# Sheet1.net
KiCad netlist of a schematic drawn in Altium Designer
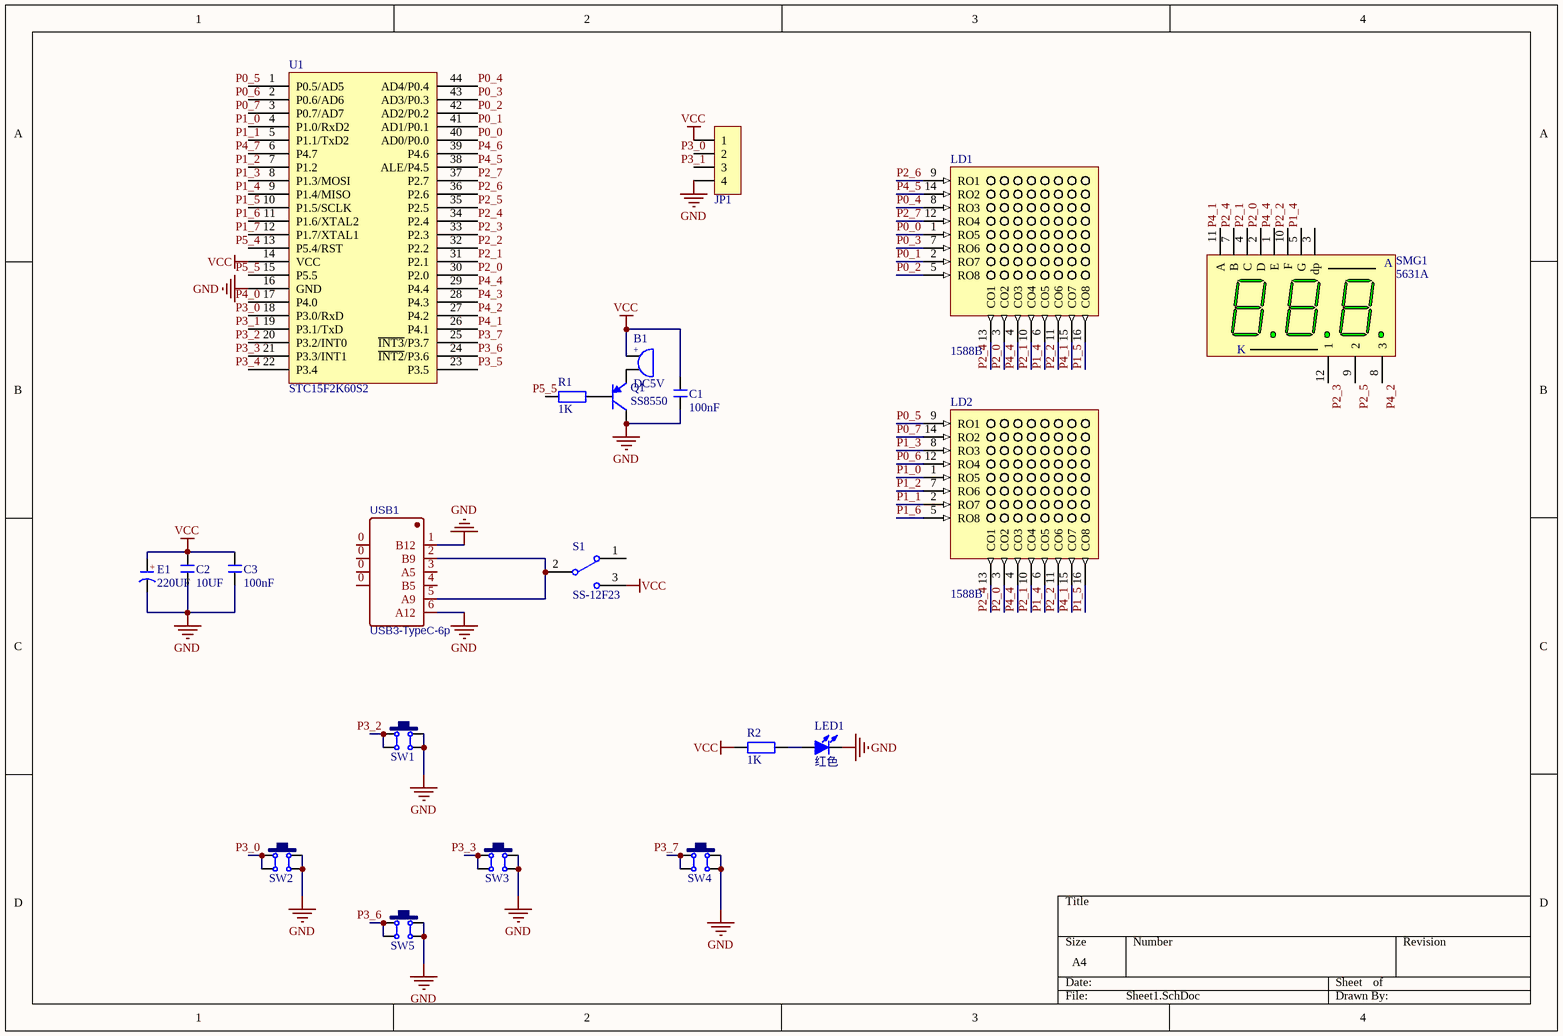
[diagram p0: Sheet1.SchDoc]

(export (version "E")
  (design (tool "Eeschema 10.0.6"))
  (components
    (comp (ref "B1")
      (value "DC5V")
      (footprint "BEEP 5x9x5.5")
      (description "蜂鸣器")
      (fields (field (name "版权归属") "黎明电子style"))
      (libsource (lib "1.7.1-未分类器件") (part "BEEP"))
    )
    (comp (ref "C1")
      (value "100nF")
      (footprint "C 0805")
      (description "无极性贴片电容")
      (fields (field (name "版权归属") "黎明电子style"))
      (libsource (lib "1.3.2-电阻_电容_电感") (part "C"))
    )
    (comp (ref "C2")
      (value "10UF")
      (footprint "C 0805")
      (description "无极性贴片电容")
      (fields (field (name "版权归属") "黎明电子style"))
      (libsource (lib "1.3.2-电阻_电容_电感") (part "C"))
    )
    (comp (ref "C3")
      (value "100nF")
      (footprint "C 0805")
      (description "无极性贴片电容")
      (fields (field (name "版权归属") "黎明电子style"))
      (libsource (lib "1.3.2-电阻_电容_电感") (part "C"))
    )
    (comp (ref "E1")
      (value "220UF")
      (footprint "CAP 2.5*5*11 - BK")
      (description "直插电解电容")
      (fields (field (name "版权归属") "黎明电子style"))
      (libsource (lib "1.3.2-电阻_电容_电感") (part "C-CAP"))
    )
    (comp (ref "JP1")
      (value "HDR-1X4")
      (footprint "HDR2.54-WS-4P")
      (description "4P接插件")
      (fields (field (name "版权归属") "黎明电子style"))
      (libsource (lib "1.5.1-接插件") (part "Header 4"))
    )
    (comp (ref "LD1")
      (value "1588B")
      (footprint "LED 8*8-38")
      (description "共阳单色LED8*8点阵屏")
      (fields (field (name "版权归属") "黎明电子style"))
      (libsource (lib "1.6.6-点阵屏_屏幕") (part "1588B"))
    )
    (comp (ref "LD2")
      (value "1588B")
      (footprint "LED 8*8-38")
      (description "共阳单色LED8*8点阵屏")
      (fields (field (name "版权归属") "黎明电子style"))
      (libsource (lib "1.6.6-点阵屏_屏幕") (part "1588B"))
    )
    (comp (ref "LED1")
      (value "红色")
      (footprint "LED 0805G")
      (description "贴片LED")
      (fields (field (name "版权归属") "黎明电子style"))
      (libsource (lib "1.3.1-LED") (part "LED-SMD"))
    )
    (comp (ref "Q1")
      (value "SS8550")
      (footprint "SOT23-3M")
      (description "高频放大-PNP型")
      (fields (field (name "版权归属") "源创客"))
      (libsource (lib "1.3.4-三极管") (part "8550-SMD"))
    )
    (comp (ref "R1")
      (value "1K")
      (footprint "R 0805")
      (description "贴片电阻")
      (fields (field (name "版权归属") "黎明电子style"))
      (libsource (lib "1.3.2-电阻_电容_电感") (part "R"))
    )
    (comp (ref "R2")
      (value "1K")
      (footprint "R 0805")
      (description "贴片电阻")
      (fields (field (name "版权归属") "黎明电子style"))
      (libsource (lib "1.3.2-电阻_电容_电感") (part "R"))
    )
    (comp (ref "S1")
      (value "SS-12F23")
      (footprint "SS-12D10")
      (description "1路波动开关")
      (fields (field (name "版权归属") "黎明电子style"))
      (libsource (lib "1.4.1-按键-开关") (part "SSW-1P"))
    )
    (comp (ref "SMG1")
      (value "5631A")
      (footprint "SMG 0.56-3P")
      (description "0.56寸3位共阴数码管")
      (fields (field (name "版权归属") "黎明电子style"))
      (libsource (lib "1.6.5-数码管") (part "5631A"))
    )
    (comp (ref "SW1")
      (value "6x6x5")
      (footprint "TSW DIP-6*6*6")
      (description "直插6x6轻触开关")
      (fields (field (name "版权归属") "黎明电子style"))
      (libsource (lib "1.4.1-按键-开关") (part "TSW DIP-6x6"))
    )
    (comp (ref "SW2")
      (value "6x6x5")
      (footprint "TSW DIP-6*6*6")
      (description "直插6x6轻触开关")
      (fields (field (name "版权归属") "黎明电子style"))
      (libsource (lib "1.4.1-按键-开关") (part "TSW DIP-6x6"))
    )
    (comp (ref "SW3")
      (value "6x6x5")
      (footprint "TSW DIP-6*6*6")
      (description "直插6x6轻触开关")
      (fields (field (name "版权归属") "黎明电子style"))
      (libsource (lib "1.4.1-按键-开关") (part "TSW DIP-6x6"))
    )
    (comp (ref "SW4")
      (value "6x6x5")
      (footprint "TSW DIP-6*6*6")
      (description "直插6x6轻触开关")
      (fields (field (name "版权归属") "黎明电子style"))
      (libsource (lib "1.4.1-按键-开关") (part "TSW DIP-6x6"))
    )
    (comp (ref "SW5")
      (value "6x6x5")
      (footprint "TSW DIP-6*6*6")
      (description "直插6x6轻触开关")
      (fields (field (name "版权归属") "黎明电子style"))
      (libsource (lib "1.4.1-按键-开关") (part "TSW DIP-6x6"))
    )
    (comp (ref "U1")
      (value "STC15F2K60S2")
      (footprint "LQFP44 10X10_M")
      (description "STC单片机")
      (fields (field (name "版权归属") "校基地硬件部"))
      (libsource (lib "1.2.1-STC系列单片机") (part "STC15F2K60S2-44pin"))
    )
    (comp (ref "USB1")
      (value "USB3-TypeC-6p")
      (footprint "USB-TYPE-C-SMD6")
      (libsource (lib "type-c-sch") (part "USB3-TypeC-6p"))
    )
  )
  (nets
    (net (code "1") (name "/P0_0") (class "Default")
      (node (ref "LD1") (pin "1") (pinfunction "RO5_1") (pintype "input"))
      (node (ref "U1") (pin "40") (pinfunction "AD0/P0.0_40") (pintype "passive"))
    )
    (net (code "2") (name "/P0_1") (class "Default")
      (node (ref "LD1") (pin "2") (pinfunction "RO7_2") (pintype "input"))
      (node (ref "U1") (pin "41") (pinfunction "AD1/P0.1_41") (pintype "passive"))
    )
    (net (code "3") (name "/P0_2") (class "Default")
      (node (ref "LD1") (pin "5") (pinfunction "RO8_5") (pintype "input"))
      (node (ref "U1") (pin "42") (pinfunction "AD2/P0.2_42") (pintype "passive"))
    )
    (net (code "4") (name "/P0_3") (class "Default")
      (node (ref "LD1") (pin "7") (pinfunction "RO6_7") (pintype "input"))
      (node (ref "U1") (pin "43") (pinfunction "AD3/P0.3_43") (pintype "passive"))
    )
    (net (code "5") (name "/P0_4") (class "Default")
      (node (ref "LD1") (pin "8") (pinfunction "RO3_8") (pintype "input"))
      (node (ref "U1") (pin "44") (pinfunction "AD4/P0.4_44") (pintype "passive"))
    )
    (net (code "6") (name "/P0_5") (class "Default")
      (node (ref "LD2") (pin "9") (pinfunction "RO1_9") (pintype "input"))
      (node (ref "U1") (pin "1") (pinfunction "P0.5/AD5_1") (pintype "passive"))
    )
    (net (code "7") (name "/P0_6") (class "Default")
      (node (ref "LD2") (pin "12") (pinfunction "RO4_12") (pintype "input"))
      (node (ref "U1") (pin "2") (pinfunction "P0.6/AD6_2") (pintype "passive"))
    )
    (net (code "8") (name "/P0_7") (class "Default")
      (node (ref "LD2") (pin "14") (pinfunction "RO2_14") (pintype "input"))
      (node (ref "U1") (pin "3") (pinfunction "P0.7/AD7_3") (pintype "passive"))
    )
    (net (code "9") (name "/P1_0") (class "Default")
      (node (ref "LD2") (pin "1") (pinfunction "RO5_1") (pintype "input"))
      (node (ref "U1") (pin "4") (pinfunction "P1.0/RxD2_4") (pintype "passive"))
    )
    (net (code "10") (name "/P1_1") (class "Default")
      (node (ref "LD2") (pin "2") (pinfunction "RO7_2") (pintype "input"))
      (node (ref "U1") (pin "5") (pinfunction "P1.1/TxD2_5") (pintype "passive"))
    )
    (net (code "11") (name "/P1_2") (class "Default")
      (node (ref "LD2") (pin "7") (pinfunction "RO6_7") (pintype "input"))
      (node (ref "U1") (pin "7") (pinfunction "P1.2_7") (pintype "passive"))
    )
    (net (code "12") (name "/P1_3") (class "Default")
      (node (ref "LD2") (pin "8") (pinfunction "RO3_8") (pintype "input"))
      (node (ref "U1") (pin "8") (pinfunction "P1.3/MOSI_8") (pintype "passive"))
    )
    (net (code "13") (name "/P1_4") (class "Default")
      (node (ref "LD1") (pin "6") (pinfunction "CO5_6") (pintype "output"))
      (node (ref "LD2") (pin "6") (pinfunction "CO5_6") (pintype "output"))
      (node (ref "SMG1") (pin "5") (pinfunction "G_5") (pintype "passive"))
      (node (ref "U1") (pin "9") (pinfunction "P1.4/MISO_9") (pintype "passive"))
    )
    (net (code "14") (name "/P1_5") (class "Default")
      (node (ref "LD1") (pin "16") (pinfunction "CO8_16") (pintype "output"))
      (node (ref "LD2") (pin "16") (pinfunction "CO8_16") (pintype "output"))
      (node (ref "U1") (pin "10") (pinfunction "P1.5/SCLK_10") (pintype "passive"))
    )
    (net (code "15") (name "/P1_6") (class "Default")
      (node (ref "LD2") (pin "5") (pinfunction "RO8_5") (pintype "input"))
      (node (ref "U1") (pin "11") (pinfunction "P1.6/XTAL2_11") (pintype "passive"))
    )
    (net (code "16") (name "/P1_7") (class "Default")
      (node (ref "U1") (pin "12") (pinfunction "P1.7/XTAL1_12") (pintype "passive"))
    )
    (net (code "17") (name "/P2_0") (class "Default")
      (node (ref "LD1") (pin "3") (pinfunction "CO2_3") (pintype "output"))
      (node (ref "LD2") (pin "3") (pinfunction "CO2_3") (pintype "output"))
      (node (ref "SMG1") (pin "2") (pinfunction "D_2") (pintype "passive"))
      (node (ref "U1") (pin "30") (pinfunction "P2.0_30") (pintype "passive"))
    )
    (net (code "18") (name "/P2_1") (class "Default")
      (node (ref "LD1") (pin "10") (pinfunction "CO4_10") (pintype "output"))
      (node (ref "LD2") (pin "10") (pinfunction "CO4_10") (pintype "output"))
      (node (ref "SMG1") (pin "4") (pinfunction "C_4") (pintype "passive"))
      (node (ref "U1") (pin "31") (pinfunction "P2.1_31") (pintype "passive"))
    )
    (net (code "19") (name "/P2_2") (class "Default")
      (node (ref "LD1") (pin "11") (pinfunction "CO6_11") (pintype "output"))
      (node (ref "LD2") (pin "11") (pinfunction "CO6_11") (pintype "output"))
      (node (ref "SMG1") (pin "10") (pinfunction "F_10") (pintype "passive"))
      (node (ref "U1") (pin "32") (pinfunction "P2.2_32") (pintype "passive"))
    )
    (net (code "20") (name "/P2_3") (class "Default")
      (node (ref "SMG1") (pin "12") (pinfunction "1_12") (pintype "passive"))
      (node (ref "U1") (pin "33") (pinfunction "P2.3_33") (pintype "passive"))
    )
    (net (code "21") (name "/P2_4") (class "Default")
      (node (ref "LD1") (pin "13") (pinfunction "CO1_13") (pintype "output"))
      (node (ref "LD2") (pin "13") (pinfunction "CO1_13") (pintype "output"))
      (node (ref "SMG1") (pin "7") (pinfunction "B_7") (pintype "passive"))
      (node (ref "U1") (pin "34") (pinfunction "P2.4_34") (pintype "passive"))
    )
    (net (code "22") (name "/P2_5") (class "Default")
      (node (ref "SMG1") (pin "9") (pinfunction "2_9") (pintype "passive"))
      (node (ref "U1") (pin "35") (pinfunction "P2.5_35") (pintype "passive"))
    )
    (net (code "23") (name "/P2_6") (class "Default")
      (node (ref "LD1") (pin "9") (pinfunction "RO1_9") (pintype "input"))
      (node (ref "U1") (pin "36") (pinfunction "P2.6_36") (pintype "passive"))
    )
    (net (code "24") (name "/P2_7") (class "Default")
      (node (ref "LD1") (pin "12") (pinfunction "RO4_12") (pintype "input"))
      (node (ref "U1") (pin "37") (pinfunction "P2.7_37") (pintype "passive"))
    )
    (net (code "25") (name "/P3_0") (class "Default")
      (node (ref "JP1") (pin "2") (pinfunction "2_2") (pintype "passive"))
      (node (ref "SW2") (pin "1") (pinfunction "1_1") (pintype "passive"))
      (node (ref "SW2") (pin "4") (pinfunction "4_4") (pintype "passive"))
      (node (ref "U1") (pin "18") (pinfunction "P3.0/RxD_18") (pintype "passive"))
    )
    (net (code "26") (name "/P3_1") (class "Default")
      (node (ref "JP1") (pin "3") (pinfunction "3_3") (pintype "passive"))
      (node (ref "U1") (pin "19") (pinfunction "P3.1/TxD_19") (pintype "passive"))
    )
    (net (code "27") (name "/P3_2") (class "Default")
      (node (ref "SW1") (pin "1") (pinfunction "1_1") (pintype "passive"))
      (node (ref "SW1") (pin "4") (pinfunction "4_4") (pintype "passive"))
      (node (ref "U1") (pin "20") (pinfunction "P3.2/INT0_20") (pintype "passive"))
    )
    (net (code "28") (name "/P3_3") (class "Default")
      (node (ref "SW3") (pin "1") (pinfunction "1_1") (pintype "passive"))
      (node (ref "SW3") (pin "4") (pinfunction "4_4") (pintype "passive"))
      (node (ref "U1") (pin "21") (pinfunction "P3.3/INT1_21") (pintype "passive"))
    )
    (net (code "29") (name "/P3_4") (class "Default")
      (node (ref "U1") (pin "22") (pinfunction "P3.4_22") (pintype "passive"))
    )
    (net (code "30") (name "/P3_5") (class "Default")
      (node (ref "U1") (pin "23") (pinfunction "P3.5_23") (pintype "passive"))
    )
    (net (code "31") (name "/P3_6") (class "Default")
      (node (ref "SW5") (pin "1") (pinfunction "1_1") (pintype "passive"))
      (node (ref "SW5") (pin "4") (pinfunction "4_4") (pintype "passive"))
      (node (ref "U1") (pin "24") (pinfunction "~{INT2}/P3.6_24") (pintype "passive"))
    )
    (net (code "32") (name "/P3_7") (class "Default")
      (node (ref "SW4") (pin "1") (pinfunction "1_1") (pintype "passive"))
      (node (ref "SW4") (pin "4") (pinfunction "4_4") (pintype "passive"))
      (node (ref "U1") (pin "25") (pinfunction "~{INT3}/P3.7_25") (pintype "passive"))
    )
    (net (code "33") (name "/P4_0") (class "Default")
      (node (ref "U1") (pin "17") (pinfunction "P4.0_17") (pintype "passive"))
    )
    (net (code "34") (name "/P4_1") (class "Default")
      (node (ref "LD1") (pin "15") (pinfunction "CO7_15") (pintype "output"))
      (node (ref "LD2") (pin "15") (pinfunction "CO7_15") (pintype "output"))
      (node (ref "SMG1") (pin "11") (pinfunction "A_11") (pintype "passive"))
      (node (ref "U1") (pin "26") (pinfunction "P4.1_26") (pintype "passive"))
    )
    (net (code "35") (name "/P4_2") (class "Default")
      (node (ref "SMG1") (pin "8") (pinfunction "3_8") (pintype "passive"))
      (node (ref "U1") (pin "27") (pinfunction "P4.2_27") (pintype "passive"))
    )
    (net (code "36") (name "/P4_3") (class "Default")
      (node (ref "U1") (pin "28") (pinfunction "P4.3_28") (pintype "passive"))
    )
    (net (code "37") (name "/P4_4") (class "Default")
      (node (ref "LD1") (pin "4") (pinfunction "CO3_4") (pintype "output"))
      (node (ref "LD2") (pin "4") (pinfunction "CO3_4") (pintype "output"))
      (node (ref "SMG1") (pin "1") (pinfunction "E_1") (pintype "passive"))
      (node (ref "U1") (pin "29") (pinfunction "P4.4_29") (pintype "passive"))
    )
    (net (code "38") (name "/P4_5") (class "Default")
      (node (ref "LD1") (pin "14") (pinfunction "RO2_14") (pintype "input"))
      (node (ref "U1") (pin "38") (pinfunction "ALE/P4.5_38") (pintype "passive"))
    )
    (net (code "39") (name "/P4_6") (class "Default")
      (node (ref "U1") (pin "39") (pinfunction "P4.6_39") (pintype "passive"))
    )
    (net (code "40") (name "/P4_7") (class "Default")
      (node (ref "U1") (pin "6") (pinfunction "P4.7_6") (pintype "passive"))
    )
    (net (code "41") (name "/P5_4") (class "Default")
      (node (ref "U1") (pin "13") (pinfunction "P5.4/RST_13") (pintype "passive"))
    )
    (net (code "42") (name "/P5_5") (class "Default")
      (node (ref "R1") (pin "1") (pinfunction "1_1") (pintype "passive"))
      (node (ref "U1") (pin "15") (pinfunction "P5.5_15") (pintype "passive"))
    )
    (net (code "43") (name "GND") (class "Default")
      (node (ref "C1") (pin "1") (pinfunction "1_1") (pintype "passive"))
      (node (ref "C2") (pin "1") (pinfunction "1_1") (pintype "passive"))
      (node (ref "C3") (pin "1") (pinfunction "1_1") (pintype "passive"))
      (node (ref "E1") (pin "2") (pinfunction "K_2") (pintype "passive"))
      (node (ref "JP1") (pin "4") (pinfunction "4_4") (pintype "passive"))
      (node (ref "LED1") (pin "2") (pinfunction "K_2") (pintype "passive"))
      (node (ref "Q1") (pin "3") (pinfunction "C_3") (pintype "passive"))
      (node (ref "SW1") (pin "2") (pinfunction "2_2") (pintype "passive"))
      (node (ref "SW1") (pin "3") (pinfunction "3_3") (pintype "passive"))
      (node (ref "SW2") (pin "2") (pinfunction "2_2") (pintype "passive"))
      (node (ref "SW2") (pin "3") (pinfunction "3_3") (pintype "passive"))
      (node (ref "SW3") (pin "2") (pinfunction "2_2") (pintype "passive"))
      (node (ref "SW3") (pin "3") (pinfunction "3_3") (pintype "passive"))
      (node (ref "SW4") (pin "2") (pinfunction "2_2") (pintype "passive"))
      (node (ref "SW4") (pin "3") (pinfunction "3_3") (pintype "passive"))
      (node (ref "SW5") (pin "2") (pinfunction "2_2") (pintype "passive"))
      (node (ref "SW5") (pin "3") (pinfunction "3_3") (pintype "passive"))
      (node (ref "U1") (pin "16") (pinfunction "GND_16") (pintype "passive"))
      (node (ref "USB1") (pin "1") (pinfunction "B12_1") (pintype "passive"))
      (node (ref "USB1") (pin "6") (pinfunction "A12_6") (pintype "passive"))
    )
    (net (code "44") (name "Net-(LED1-A)") (class "Default")
      (node (ref "LED1") (pin "1") (pinfunction "A_1") (pintype "passive"))
      (node (ref "R2") (pin "2") (pinfunction "2_2") (pintype "passive"))
    )
    (net (code "45") (name "Net-(Q1-B)") (class "Default")
      (node (ref "Q1") (pin "1") (pinfunction "B_1") (pintype "passive"))
      (node (ref "R1") (pin "2") (pinfunction "2_2") (pintype "passive"))
    )
    (net (code "46") (name "Net-(Q1-E)") (class "Default")
      (node (ref "B1") (pin "2") (pinfunction "2_2") (pintype "passive"))
      (node (ref "Q1") (pin "2") (pinfunction "E_2") (pintype "passive"))
    )
    (net (code "47") (name "Net-(USB1-A9)") (class "Default")
      (node (ref "S1") (pin "2") (pinfunction "2_2") (pintype "passive"))
      (node (ref "USB1") (pin "2") (pinfunction "B9_2") (pintype "passive"))
      (node (ref "USB1") (pin "5") (pinfunction "A9_5") (pintype "passive"))
    )
    (net (code "48") (name "VCC") (class "Default")
      (node (ref "B1") (pin "1") (pinfunction "1_1") (pintype "passive"))
      (node (ref "C1") (pin "2") (pinfunction "2_2") (pintype "passive"))
      (node (ref "C2") (pin "2") (pinfunction "2_2") (pintype "passive"))
      (node (ref "C3") (pin "2") (pinfunction "2_2") (pintype "passive"))
      (node (ref "E1") (pin "1") (pinfunction "A_1") (pintype "passive"))
      (node (ref "JP1") (pin "1") (pinfunction "1_1") (pintype "passive"))
      (node (ref "R2") (pin "1") (pinfunction "1_1") (pintype "passive"))
      (node (ref "S1") (pin "3") (pinfunction "3_3") (pintype "passive"))
      (node (ref "U1") (pin "14") (pinfunction "VCC_14") (pintype "passive"))
    )
    (net (code "49") (name "unconnected-(S1-Pad1)") (class "Default")
      (node (ref "S1") (pin "1") (pinfunction "1_1") (pintype "passive"))
    )
    (net (code "50") (name "unconnected-(SMG1-dp-Pad3)") (class "Default")
      (node (ref "SMG1") (pin "3") (pinfunction "dp_3") (pintype "passive"))
    )
    (net (code "51") (name "unconnected-(USB1-A5-Pad3)") (class "Default")
      (node (ref "USB1") (pin "3") (pinfunction "A5_3") (pintype "passive"))
    )
    (net (code "52") (name "unconnected-(USB1-B5-Pad4)") (class "Default")
      (node (ref "USB1") (pin "4") (pinfunction "B5_4") (pintype "passive"))
    )
    (net (code "53") (name "unconnected-(USB1-Pad0)") (class "Default")
      (node (ref "USB1") (pin "0") (pinfunction "0_0") (pintype "passive"))
    )
    (net (code "54") (name "unconnected-(USB1-Pad0)_1") (class "Default")
      (node (ref "USB1") (pin "0") (pinfunction "0_0") (pintype "passive"))
    )
    (net (code "55") (name "unconnected-(USB1-Pad0)_2") (class "Default")
      (node (ref "USB1") (pin "0") (pinfunction "0_0") (pintype "passive"))
    )
    (net (code "56") (name "unconnected-(USB1-Pad0)_3") (class "Default")
      (node (ref "USB1") (pin "0") (pinfunction "0_0") (pintype "passive"))
    )
  )
)
